# STorM32_NT_imu_v21_mini-mpu9250.net
KiCad netlist of a schematic drawn in EAGLE
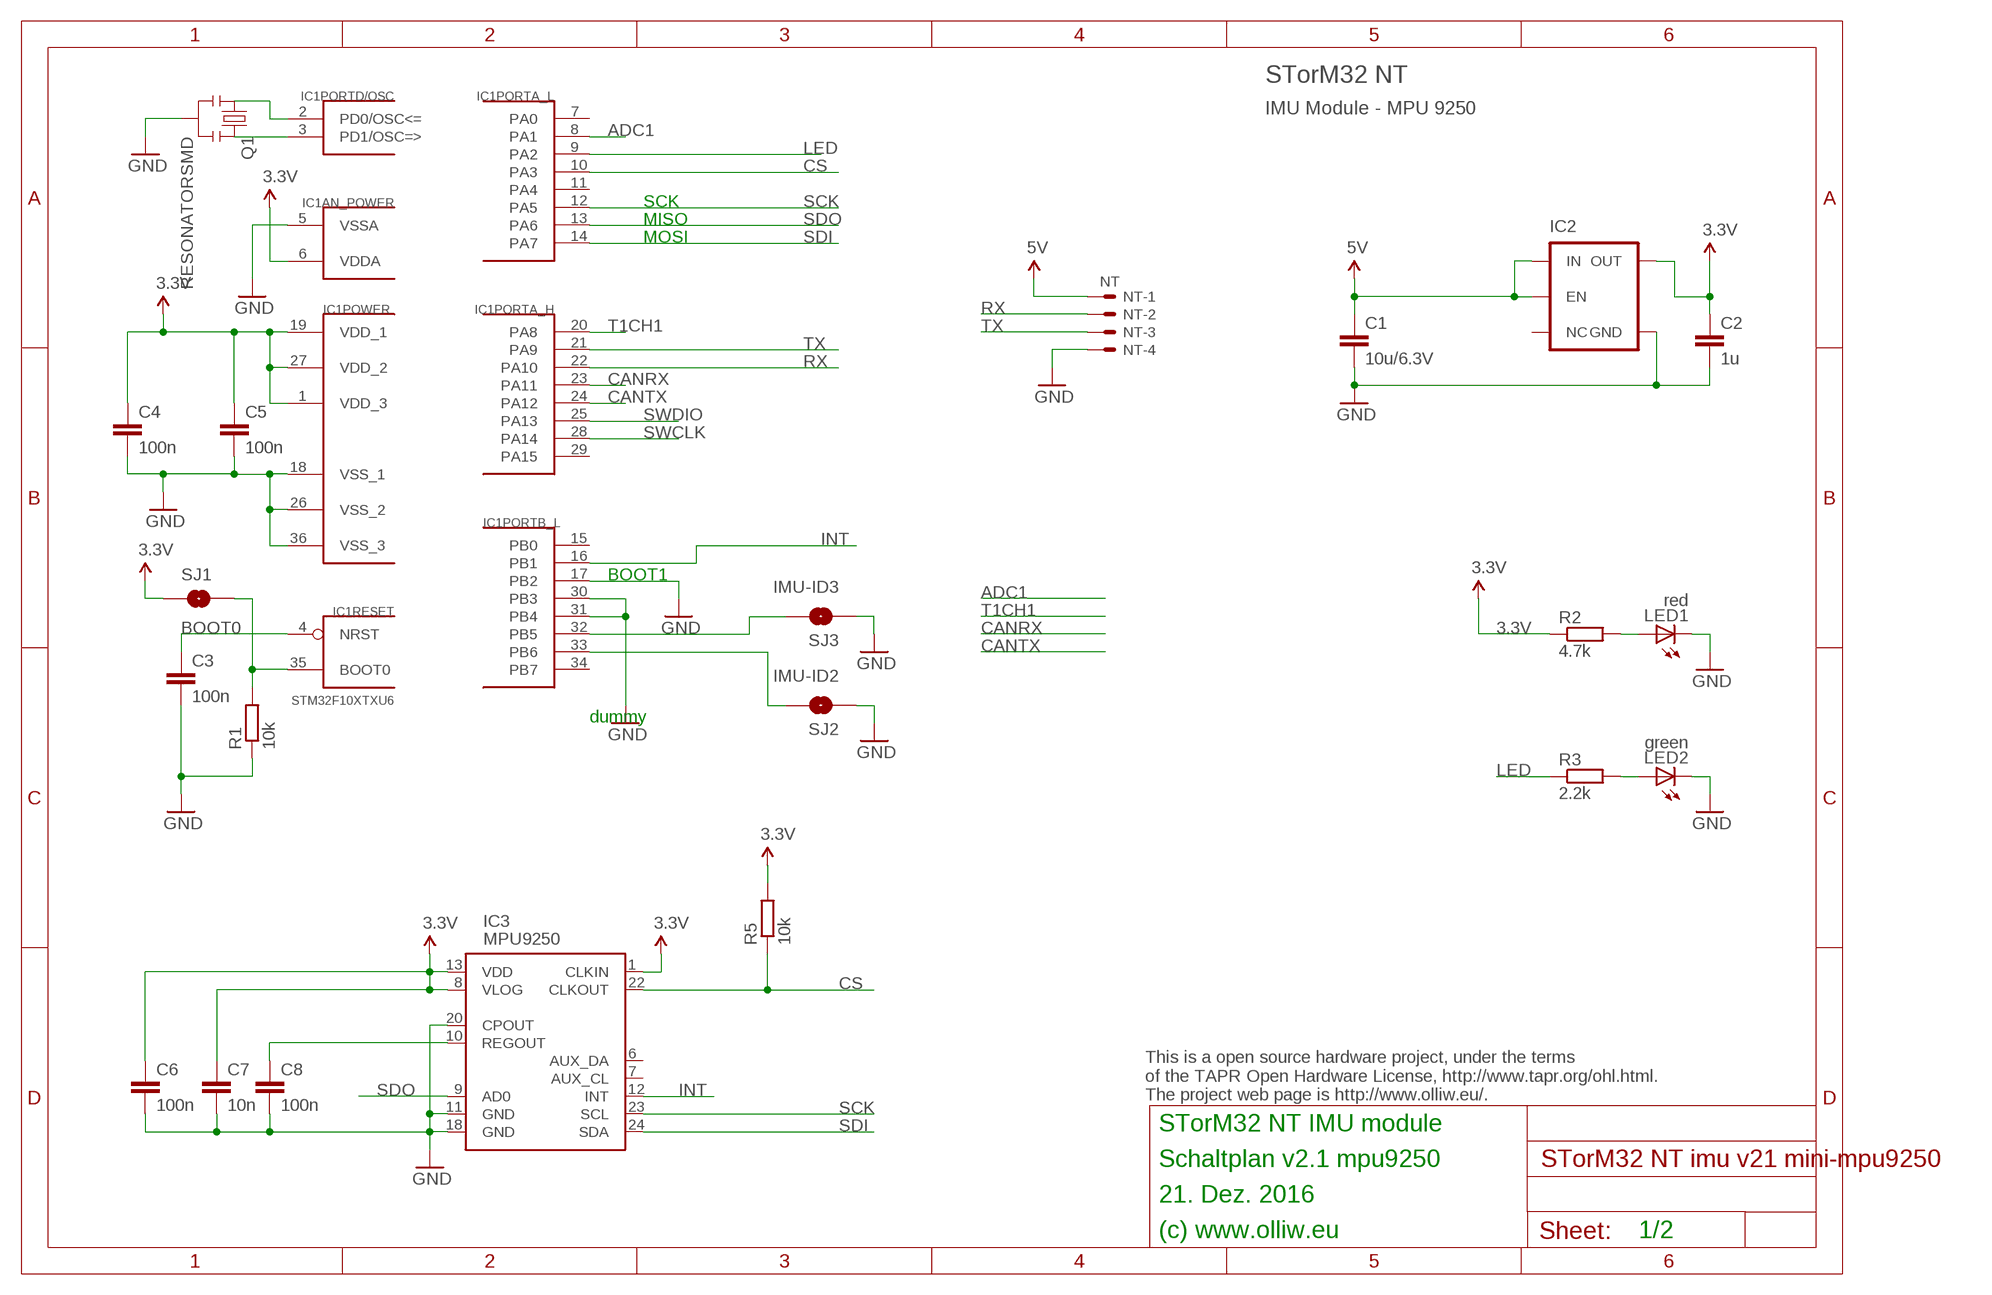
[diagram p0: schematic, sheet 1]

(export (version "E")
  (design (tool "Eeschema 10.0.6"))
  (components
    (comp (ref "C1")
      (value "10u/6.3V")
      (footprint "eagle-import:C0805")
      (libsource (lib "eagle-import") (part "C-EUC0805"))
    )
    (comp (ref "C2")
      (value "1u")
      (footprint "eagle-import:C0603")
      (libsource (lib "eagle-import") (part "C-EUC0603"))
    )
    (comp (ref "C3")
      (value "100n")
      (footprint "eagle-import:C0402")
      (libsource (lib "eagle-import") (part "C-EUC0402"))
    )
    (comp (ref "C4")
      (value "100n")
      (footprint "eagle-import:C0402")
      (libsource (lib "eagle-import") (part "C-EUC0402"))
    )
    (comp (ref "C5")
      (value "100n")
      (footprint "eagle-import:C0402")
      (libsource (lib "eagle-import") (part "C-EUC0402"))
    )
    (comp (ref "C6")
      (value "100n")
      (footprint "eagle-import:C0402")
      (libsource (lib "eagle-import") (part "C-EUC0402"))
    )
    (comp (ref "C7")
      (value "10n")
      (footprint "eagle-import:C0402")
      (libsource (lib "eagle-import") (part "C-EUC0402"))
    )
    (comp (ref "C8")
      (value "100n")
      (footprint "eagle-import:C0402")
      (libsource (lib "eagle-import") (part "C-EUC0402"))
    )
    (comp (ref "IC1")
      (value "STM32F10XTXU6")
      (footprint "eagle-import:VFQFPN36")
      (libsource (lib "eagle-import") (part "STM32F10XTXU6"))
    )
    (comp (ref "IC2")
      (value "V_REG_TPS76433SOT23-5")
      (footprint "eagle-import:SOT23-5")
      (libsource (lib "eagle-import") (part "V_REG_TPS76433SOT23-5"))
    )
    (comp (ref "IC3")
      (value "MPU9250")
      (footprint "eagle-import:QFN-24-3X3")
      (libsource (lib "eagle-import") (part "IMU3000QFN-24-0.4MIL"))
    )
    (comp (ref "LED1")
      (value "red")
      (footprint "eagle-import:CHIPLED_0603")
      (libsource (lib "eagle-import") (part "LEDCHIPLED_0603"))
    )
    (comp (ref "LED2")
      (value "green")
      (footprint "eagle-import:CHIPLED_0603")
      (libsource (lib "eagle-import") (part "LEDCHIPLED_0603"))
    )
    (comp (ref "NT")
      (value "NT")
      (footprint "eagle-import:SM04B-SRSS-TB")
      (libsource (lib "eagle-import") (part "?M04B-SRSS-TBS"))
    )
    (comp (ref "Q1")
      (value "RESONATORSMD")
      (footprint "eagle-import:RESONATOR-SMD")
      (libsource (lib "eagle-import") (part "RESONATORSMD"))
    )
    (comp (ref "R1")
      (value "10k")
      (footprint "eagle-import:R0402")
      (libsource (lib "eagle-import") (part "R-EU_R0402"))
    )
    (comp (ref "R2")
      (value "4.7k")
      (footprint "eagle-import:R0402")
      (libsource (lib "eagle-import") (part "R-EU_R0402"))
    )
    (comp (ref "R3")
      (value "2.2k")
      (footprint "eagle-import:R0402")
      (libsource (lib "eagle-import") (part "R-EU_R0402"))
    )
    (comp (ref "R5")
      (value "10k")
      (footprint "eagle-import:R0402")
      (libsource (lib "eagle-import") (part "R-EU_R0402"))
    )
    (comp (ref "SJ1")
      (value "BOOT0")
      (footprint "eagle-import:SJ_2S-NO")
      (libsource (lib "eagle-import") (part "SOLDERJUMPERNO"))
    )
    (comp (ref "SJ2")
      (value "IMU-ID2")
      (footprint "eagle-import:SJ_2S-NO")
      (libsource (lib "eagle-import") (part "SOLDERJUMPERNO"))
    )
    (comp (ref "SJ3")
      (value "IMU-ID3")
      (footprint "eagle-import:SJ_2S-NO")
      (libsource (lib "eagle-import") (part "SOLDERJUMPERNO"))
    )
  )
  (nets
    (net (code "1") (name "/ADC1") (class "Default")
      (node (ref "IC1") (pin "8") (pinfunction "PA1_8") (pintype "bidirectional"))
    )
    (net (code "2") (name "/CANRX") (class "Default")
      (node (ref "IC1") (pin "23") (pinfunction "PA11_23") (pintype "bidirectional"))
    )
    (net (code "3") (name "/CANTX") (class "Default")
      (node (ref "IC1") (pin "24") (pinfunction "PA12_24") (pintype "bidirectional"))
    )
    (net (code "4") (name "/CS") (class "Default")
      (node (ref "IC1") (pin "10") (pinfunction "PA3_10") (pintype "bidirectional"))
      (node (ref "IC3") (pin "22") (pinfunction "CLKOUT_22") (pintype "bidirectional"))
      (node (ref "R5") (pin "1") (pinfunction "1_1") (pintype "passive"))
    )
    (net (code "5") (name "/INT") (class "Default")
      (node (ref "IC1") (pin "16") (pinfunction "PB1_16") (pintype "bidirectional"))
      (node (ref "IC3") (pin "12") (pinfunction "INT_12") (pintype "bidirectional"))
    )
    (net (code "6") (name "/LED") (class "Default")
      (node (ref "IC1") (pin "9") (pinfunction "PA2_9") (pintype "bidirectional"))
      (node (ref "R3") (pin "1") (pinfunction "1_1") (pintype "passive"))
    )
    (net (code "7") (name "/RX") (class "Default")
      (node (ref "IC1") (pin "22") (pinfunction "PA10_22") (pintype "bidirectional"))
      (node (ref "NT") (pin "2") (pinfunction "S_2") (pintype "passive"))
    )
    (net (code "8") (name "/SCK") (class "Default")
      (node (ref "IC1") (pin "12") (pinfunction "PA5_12") (pintype "bidirectional"))
      (node (ref "IC3") (pin "23") (pinfunction "SCL_23") (pintype "bidirectional"))
    )
    (net (code "9") (name "/SDI") (class "Default")
      (node (ref "IC1") (pin "14") (pinfunction "PA7_14") (pintype "bidirectional"))
      (node (ref "IC3") (pin "24") (pinfunction "SDA_24") (pintype "bidirectional"))
    )
    (net (code "10") (name "/SDO") (class "Default")
      (node (ref "IC1") (pin "13") (pinfunction "PA6_13") (pintype "bidirectional"))
      (node (ref "IC3") (pin "9") (pinfunction "AD0_9") (pintype "bidirectional"))
    )
    (net (code "11") (name "/SWCLK") (class "Default")
      (node (ref "IC1") (pin "28") (pinfunction "PA14_28") (pintype "bidirectional"))
    )
    (net (code "12") (name "/SWDIO") (class "Default")
      (node (ref "IC1") (pin "25") (pinfunction "PA13_25") (pintype "bidirectional"))
    )
    (net (code "13") (name "/T1CH1") (class "Default")
      (node (ref "IC1") (pin "20") (pinfunction "PA8_20") (pintype "bidirectional"))
    )
    (net (code "14") (name "/TX") (class "Default")
      (node (ref "IC1") (pin "21") (pinfunction "PA9_21") (pintype "bidirectional"))
      (node (ref "NT") (pin "3") (pinfunction "S_3") (pintype "passive"))
    )
    (net (code "15") (name "3.3V") (class "Default")
      (node (ref "C2") (pin "1") (pinfunction "1_1") (pintype "passive"))
      (node (ref "C4") (pin "1") (pinfunction "1_1") (pintype "passive"))
      (node (ref "C5") (pin "1") (pinfunction "1_1") (pintype "passive"))
      (node (ref "C6") (pin "1") (pinfunction "1_1") (pintype "passive"))
      (node (ref "C7") (pin "1") (pinfunction "1_1") (pintype "passive"))
      (node (ref "IC1") (pin "1") (pinfunction "VDD_3_1") (pintype "power_in"))
      (node (ref "IC1") (pin "19") (pinfunction "VDD_1_19") (pintype "power_in"))
      (node (ref "IC1") (pin "27") (pinfunction "VDD_2_27") (pintype "power_in"))
      (node (ref "IC1") (pin "6") (pinfunction "VDDA_6") (pintype "power_in"))
      (node (ref "IC2") (pin "5") (pinfunction "OUT_5") (pintype "passive"))
      (node (ref "IC3") (pin "1") (pinfunction "CLKIN_1") (pintype "bidirectional"))
      (node (ref "IC3") (pin "13") (pinfunction "VDD_13") (pintype "bidirectional"))
      (node (ref "IC3") (pin "8") (pinfunction "VLOG_8") (pintype "bidirectional"))
      (node (ref "R2") (pin "1") (pinfunction "1_1") (pintype "passive"))
      (node (ref "R5") (pin "2") (pinfunction "2_2") (pintype "passive"))
      (node (ref "SJ1") (pin "1") (pinfunction "1_1") (pintype "passive"))
    )
    (net (code "16") (name "5V") (class "Default")
      (node (ref "C1") (pin "1") (pinfunction "1_1") (pintype "passive"))
      (node (ref "IC2") (pin "1") (pinfunction "IN_1") (pintype "input"))
      (node (ref "IC2") (pin "3") (pinfunction "EN_3") (pintype "input"))
      (node (ref "NT") (pin "1") (pinfunction "S_1") (pintype "passive"))
    )
    (net (code "17") (name "GND") (class "Default")
      (node (ref "C1") (pin "2") (pinfunction "2_2") (pintype "passive"))
      (node (ref "C2") (pin "2") (pinfunction "2_2") (pintype "passive"))
      (node (ref "C3") (pin "2") (pinfunction "2_2") (pintype "passive"))
      (node (ref "C4") (pin "2") (pinfunction "2_2") (pintype "passive"))
      (node (ref "C5") (pin "2") (pinfunction "2_2") (pintype "passive"))
      (node (ref "C6") (pin "2") (pinfunction "2_2") (pintype "passive"))
      (node (ref "C7") (pin "2") (pinfunction "2_2") (pintype "passive"))
      (node (ref "C8") (pin "2") (pinfunction "2_2") (pintype "passive"))
      (node (ref "IC1") (pin "17") (pinfunction "PB2_17") (pintype "bidirectional"))
      (node (ref "IC1") (pin "18") (pinfunction "VSS_1_18") (pintype "power_in"))
      (node (ref "IC1") (pin "26") (pinfunction "VSS_2_26") (pintype "power_in"))
      (node (ref "IC1") (pin "30") (pinfunction "PB3_30") (pintype "bidirectional"))
      (node (ref "IC1") (pin "31") (pinfunction "PB4_31") (pintype "bidirectional"))
      (node (ref "IC1") (pin "36") (pinfunction "VSS_3_36") (pintype "power_in"))
      (node (ref "IC1") (pin "5") (pinfunction "VSSA_5") (pintype "power_in"))
      (node (ref "IC2") (pin "2") (pinfunction "GND_2") (pintype "input"))
      (node (ref "IC3") (pin "11") (pinfunction "GND_11") (pintype "bidirectional"))
      (node (ref "IC3") (pin "18") (pinfunction "GND_18") (pintype "bidirectional"))
      (node (ref "IC3") (pin "20") (pinfunction "CPOUT_20") (pintype "bidirectional"))
      (node (ref "LED1") (pin "C") (pinfunction "C_C") (pintype "passive"))
      (node (ref "LED2") (pin "C") (pinfunction "C_C") (pintype "passive"))
      (node (ref "NT") (pin "4") (pinfunction "S_4") (pintype "passive"))
      (node (ref "Q1") (pin "2") (pinfunction "2_2") (pintype "passive"))
      (node (ref "R1") (pin "1") (pinfunction "1_1") (pintype "passive"))
      (node (ref "SJ2") (pin "1") (pinfunction "1_1") (pintype "passive"))
      (node (ref "SJ3") (pin "1") (pinfunction "1_1") (pintype "passive"))
    )
    (net (code "18") (name "Net-(IC1D-PB5)") (class "Default")
      (node (ref "IC1") (pin "32") (pinfunction "PB5_32") (pintype "bidirectional"))
      (node (ref "SJ3") (pin "2") (pinfunction "2_2") (pintype "passive"))
    )
    (net (code "19") (name "Net-(IC1D-PB6)") (class "Default")
      (node (ref "IC1") (pin "33") (pinfunction "PB6_33") (pintype "bidirectional"))
      (node (ref "SJ2") (pin "2") (pinfunction "2_2") (pintype "passive"))
    )
    (net (code "20") (name "Net-(IC1E-PD0{slash}OSC<=)") (class "Default")
      (node (ref "IC1") (pin "2") (pinfunction "PD0/OSC<=_2") (pintype "bidirectional"))
      (node (ref "Q1") (pin "1") (pinfunction "1_1") (pintype "passive"))
    )
    (net (code "21") (name "Net-(IC1E-PD1{slash}OSC=>)") (class "Default")
      (node (ref "IC1") (pin "3") (pinfunction "PD1/OSC=>_3") (pintype "bidirectional"))
      (node (ref "Q1") (pin "3") (pinfunction "3_3") (pintype "passive"))
    )
    (net (code "22") (name "Net-(IC1G-BOOT0)") (class "Default")
      (node (ref "IC1") (pin "35") (pinfunction "BOOT0_35") (pintype "input"))
      (node (ref "R1") (pin "2") (pinfunction "2_2") (pintype "passive"))
      (node (ref "SJ1") (pin "2") (pinfunction "2_2") (pintype "passive"))
    )
    (net (code "23") (name "Net-(IC1G-NRST)") (class "Default")
      (node (ref "C3") (pin "1") (pinfunction "1_1") (pintype "passive"))
      (node (ref "IC1") (pin "4") (pinfunction "NRST_4") (pintype "input"))
    )
    (net (code "24") (name "Net-(IC3-REGOUT)") (class "Default")
      (node (ref "C8") (pin "1") (pinfunction "1_1") (pintype "passive"))
      (node (ref "IC3") (pin "10") (pinfunction "REGOUT_10") (pintype "bidirectional"))
    )
    (net (code "25") (name "Net-(LED1-PadA)") (class "Default")
      (node (ref "LED1") (pin "A") (pinfunction "A_A") (pintype "passive"))
      (node (ref "R2") (pin "2") (pinfunction "2_2") (pintype "passive"))
    )
    (net (code "26") (name "Net-(LED2-PadA)") (class "Default")
      (node (ref "LED2") (pin "A") (pinfunction "A_A") (pintype "passive"))
      (node (ref "R3") (pin "2") (pinfunction "2_2") (pintype "passive"))
    )
    (net (code "27") (name "unconnected-(IC1B-PA15-Pad29)") (class "Default")
      (node (ref "IC1") (pin "29") (pinfunction "PA15_29") (pintype "bidirectional"))
    )
    (net (code "28") (name "unconnected-(IC1C-PA0-Pad7)") (class "Default")
      (node (ref "IC1") (pin "7") (pinfunction "PA0_7") (pintype "bidirectional"))
    )
    (net (code "29") (name "unconnected-(IC1C-PA4-Pad11)") (class "Default")
      (node (ref "IC1") (pin "11") (pinfunction "PA4_11") (pintype "bidirectional"))
    )
    (net (code "30") (name "unconnected-(IC1D-PB0-Pad15)") (class "Default")
      (node (ref "IC1") (pin "15") (pinfunction "PB0_15") (pintype "bidirectional"))
    )
    (net (code "31") (name "unconnected-(IC1D-PB7-Pad34)") (class "Default")
      (node (ref "IC1") (pin "34") (pinfunction "PB7_34") (pintype "bidirectional"))
    )
    (net (code "32") (name "unconnected-(IC2-NC-Pad4)") (class "Default")
      (node (ref "IC2") (pin "4") (pinfunction "NC_4") (pintype "input"))
    )
    (net (code "33") (name "unconnected-(IC3-AUX_CL-Pad7)") (class "Default")
      (node (ref "IC3") (pin "7") (pinfunction "AUX_CL_7") (pintype "bidirectional"))
    )
    (net (code "34") (name "unconnected-(IC3-AUX_DA-Pad6)") (class "Default")
      (node (ref "IC3") (pin "6") (pinfunction "AUX_DA_6") (pintype "bidirectional"))
    )
  )
)
